# Reflow_Control_Board_Rev_2.net
KiCad netlist of a schematic drawn in EAGLE
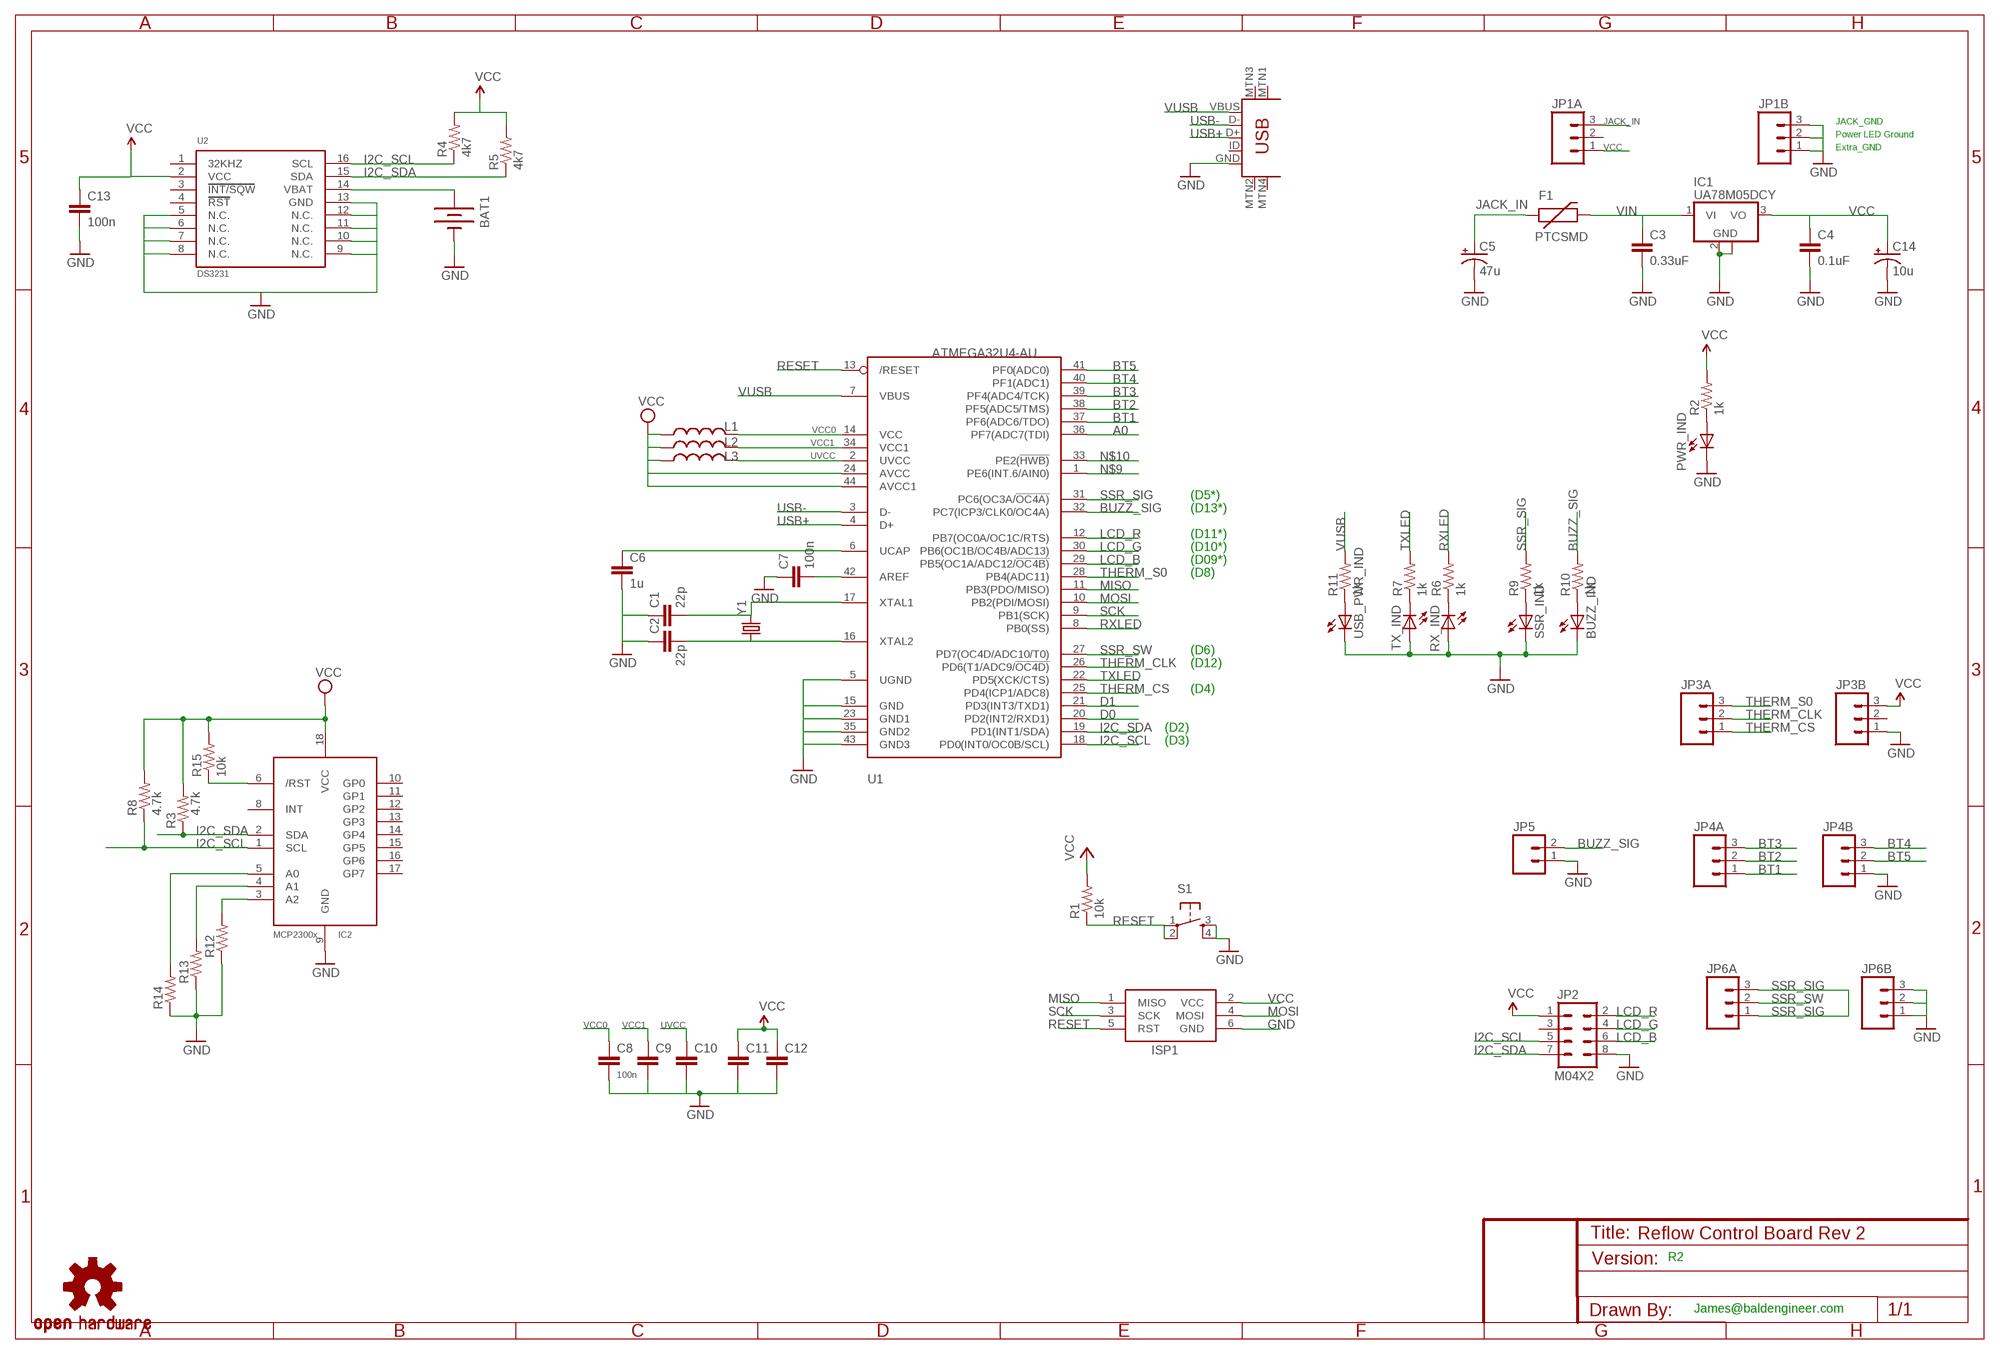
[diagram p0: schematic, sheet 1]

(export (version "E")
  (design (tool "Eeschema 10.0.6"))
  (components
    (comp (ref "BAT1")
      (value "BATTERY12MM")
      (footprint "eagle-import:BATTCON_12MM")
      (libsource (lib "eagle-import") (part "BATTERY12MM"))
    )
    (comp (ref "BUZZ_IND")
      (value "LED1206")
      (footprint "eagle-import:LED-1206")
      (libsource (lib "eagle-import") (part "LED1206"))
    )
    (comp (ref "C1")
      (value "22p")
      (footprint "eagle-import:1206")
      (libsource (lib "eagle-import") (part "CAP1206"))
    )
    (comp (ref "C2")
      (value "22p")
      (footprint "eagle-import:1206")
      (libsource (lib "eagle-import") (part "CAP1206"))
    )
    (comp (ref "C3")
      (value "0.33uF")
      (footprint "eagle-import:1206")
      (libsource (lib "eagle-import") (part "CAP1206"))
    )
    (comp (ref "C4")
      (value "0.1uF")
      (footprint "eagle-import:1206")
      (libsource (lib "eagle-import") (part "CAP1206"))
    )
    (comp (ref "C5")
      (value "47u")
      (footprint "eagle-import:D_7343-31R")
      (libsource (lib "eagle-import") (part "CPOL-USD/7343-31R"))
    )
    (comp (ref "C6")
      (value "1u")
      (footprint "eagle-import:1206")
      (libsource (lib "eagle-import") (part "CAP1206"))
    )
    (comp (ref "C7")
      (value "100n")
      (footprint "eagle-import:1206")
      (libsource (lib "eagle-import") (part "CAP1206"))
    )
    (comp (ref "C8")
      (value "100n")
      (footprint "eagle-import:1206")
      (libsource (lib "eagle-import") (part "CAP1206"))
    )
    (comp (ref "C9")
      (value "100n")
      (footprint "eagle-import:1206")
      (libsource (lib "eagle-import") (part "CAP1206"))
    )
    (comp (ref "C10")
      (value "100n")
      (footprint "eagle-import:1206")
      (libsource (lib "eagle-import") (part "CAP1206"))
    )
    (comp (ref "C11")
      (value "100n")
      (footprint "eagle-import:1206")
      (libsource (lib "eagle-import") (part "CAP1206"))
    )
    (comp (ref "C12")
      (value "100n")
      (footprint "eagle-import:1206")
      (libsource (lib "eagle-import") (part "CAP1206"))
    )
    (comp (ref "C13")
      (value "100n")
      (footprint "eagle-import:1206")
      (libsource (lib "eagle-import") (part "CAP1206"))
    )
    (comp (ref "C14")
      (value "10u")
      (footprint "eagle-import:D_7343-31R")
      (libsource (lib "eagle-import") (part "CPOL-USD/7343-31R"))
    )
    (comp (ref "F1")
      (value "PTCSMD")
      (footprint "eagle-import:PTC-1206")
      (libsource (lib "eagle-import") (part "PTCSMD"))
    )
    (comp (ref "IC1")
      (value "UA78M05DCY")
      (footprint "eagle-import:SOT223")
      (libsource (lib "eagle-import") (part "UA78MDCY05"))
    )
    (comp (ref "IC2")
      (value "MCP2300X/SO")
      (footprint "eagle-import:SO18W")
      (libsource (lib "eagle-import") (part "MCP2300X/SO"))
    )
    (comp (ref "ISP1")
      (value "AVRISP-6")
      (footprint "eagle-import:AVRISP")
      (libsource (lib "eagle-import") (part "AVRISP-6"))
    )
    (comp (ref "JP1A")
      (value "M03LOCK")
      (footprint "eagle-import:1X03_LOCK")
      (libsource (lib "eagle-import") (part "M03LOCK"))
    )
    (comp (ref "JP1B")
      (value "M03LOCK")
      (footprint "eagle-import:1X03_LOCK")
      (libsource (lib "eagle-import") (part "M03LOCK"))
    )
    (comp (ref "JP2")
      (value "M04X2")
      (footprint "eagle-import:2X4")
      (libsource (lib "eagle-import") (part "M04X2"))
    )
    (comp (ref "JP3A")
      (value "M03LOCK")
      (footprint "eagle-import:1X03_LOCK")
      (libsource (lib "eagle-import") (part "M03LOCK"))
    )
    (comp (ref "JP3B")
      (value "M03LOCK")
      (footprint "eagle-import:1X03_LOCK")
      (libsource (lib "eagle-import") (part "M03LOCK"))
    )
    (comp (ref "JP4A")
      (value "M03LOCK")
      (footprint "eagle-import:1X03_LOCK")
      (libsource (lib "eagle-import") (part "M03LOCK"))
    )
    (comp (ref "JP4B")
      (value "M03LOCK")
      (footprint "eagle-import:1X03_LOCK")
      (libsource (lib "eagle-import") (part "M03LOCK"))
    )
    (comp (ref "JP5")
      (value "M02LOCK")
      (footprint "eagle-import:1X02_LOCK")
      (libsource (lib "eagle-import") (part "M02LOCK"))
    )
    (comp (ref "JP6A")
      (value "M03LOCK")
      (footprint "eagle-import:1X03_LOCK")
      (libsource (lib "eagle-import") (part "M03LOCK"))
    )
    (comp (ref "JP6B")
      (value "M03LOCK")
      (footprint "eagle-import:1X03_LOCK")
      (libsource (lib "eagle-import") (part "M03LOCK"))
    )
    (comp (ref "L1")
      (value "INDUCTOR0805")
      (footprint "eagle-import:0805")
      (libsource (lib "eagle-import") (part "INDUCTOR0805"))
    )
    (comp (ref "L2")
      (value "INDUCTOR0805")
      (footprint "eagle-import:0805")
      (libsource (lib "eagle-import") (part "INDUCTOR0805"))
    )
    (comp (ref "L3")
      (value "INDUCTOR0805")
      (footprint "eagle-import:0805")
      (libsource (lib "eagle-import") (part "INDUCTOR0805"))
    )
    (comp (ref "PWR_IND")
      (value "LED1206")
      (footprint "eagle-import:LED-1206")
      (libsource (lib "eagle-import") (part "LED1206"))
    )
    (comp (ref "R1")
      (value "10k")
      (footprint "eagle-import:1206")
      (libsource (lib "eagle-import") (part "RESISTOR1206"))
    )
    (comp (ref "R2")
      (value "1k")
      (footprint "eagle-import:1206")
      (libsource (lib "eagle-import") (part "RESISTOR1206"))
    )
    (comp (ref "R3")
      (value "4.7k")
      (footprint "eagle-import:1206")
      (libsource (lib "eagle-import") (part "RESISTOR1206"))
    )
    (comp (ref "R4")
      (value "4k7")
      (footprint "eagle-import:1206")
      (libsource (lib "eagle-import") (part "RESISTOR1206"))
    )
    (comp (ref "R5")
      (value "4k7")
      (footprint "eagle-import:1206")
      (libsource (lib "eagle-import") (part "RESISTOR1206"))
    )
    (comp (ref "R6")
      (value "1k")
      (footprint "eagle-import:1206")
      (libsource (lib "eagle-import") (part "RESISTOR1206"))
    )
    (comp (ref "R7")
      (value "1k")
      (footprint "eagle-import:1206")
      (libsource (lib "eagle-import") (part "RESISTOR1206"))
    )
    (comp (ref "R8")
      (value "4.7k")
      (footprint "eagle-import:1206")
      (libsource (lib "eagle-import") (part "RESISTOR1206"))
    )
    (comp (ref "R9")
      (value "1k")
      (footprint "eagle-import:1206")
      (libsource (lib "eagle-import") (part "RESISTOR1206"))
    )
    (comp (ref "R10")
      (value "1k")
      (footprint "eagle-import:1206")
      (libsource (lib "eagle-import") (part "RESISTOR1206"))
    )
    (comp (ref "R11")
      (value "1k")
      (footprint "eagle-import:1206")
      (libsource (lib "eagle-import") (part "RESISTOR1206"))
    )
    (comp (ref "R12")
      (value "RESISTOR1206")
      (footprint "eagle-import:1206")
      (libsource (lib "eagle-import") (part "RESISTOR1206"))
    )
    (comp (ref "R13")
      (value "RESISTOR1206")
      (footprint "eagle-import:1206")
      (libsource (lib "eagle-import") (part "RESISTOR1206"))
    )
    (comp (ref "R14")
      (value "RESISTOR1206")
      (footprint "eagle-import:1206")
      (libsource (lib "eagle-import") (part "RESISTOR1206"))
    )
    (comp (ref "R15")
      (value "10k")
      (footprint "eagle-import:1206")
      (libsource (lib "eagle-import") (part "RESISTOR1206"))
    )
    (comp (ref "RX_IND")
      (value "LED1206")
      (footprint "eagle-import:LED-1206")
      (libsource (lib "eagle-import") (part "LED1206"))
    )
    (comp (ref "S1")
      (value "TAC_SWITCHSMD")
      (footprint "eagle-import:TACTILE_SWITCH_SMD")
      (libsource (lib "eagle-import") (part "TAC_SWITCHSMD"))
    )
    (comp (ref "SSR_IND")
      (value "LED1206")
      (footprint "eagle-import:LED-1206")
      (libsource (lib "eagle-import") (part "LED1206"))
    )
    (comp (ref "TX_IND")
      (value "LED1206")
      (footprint "eagle-import:LED-1206")
      (libsource (lib "eagle-import") (part "LED1206"))
    )
    (comp (ref "U$3")
      (value "USB-MINIB-5PIN")
      (footprint "eagle-import:USB-MINIB")
      (libsource (lib "eagle-import") (part "USB-MINIB-5PIN"))
    )
    (comp (ref "U$4")
      (value "OSHW-LOGOS")
      (footprint "eagle-import:OSHW-LOGO-S")
      (libsource (lib "eagle-import") (part "OSHW-LOGOS"))
    )
    (comp (ref "U1")
      (value "ATMEGA32U4-AU")
      (footprint "eagle-import:TQFP44")
      (libsource (lib "eagle-import") (part "ATMEGA32U4-AU"))
    )
    (comp (ref "U2")
      (value "DS3231")
      (footprint "eagle-import:SO16L")
      (libsource (lib "eagle-import") (part "DS3231"))
    )
    (comp (ref "USB_PWR_IND")
      (value "LED1206")
      (footprint "eagle-import:LED-1206")
      (libsource (lib "eagle-import") (part "LED1206"))
    )
    (comp (ref "Y1")
      (value "CRYSTALHC49US")
      (footprint "eagle-import:HC49US")
      (libsource (lib "eagle-import") (part "CRYSTALHC49US"))
    )
  )
  (nets
    (net (code "1") (name "/A0") (class "Default")
      (node (ref "U1") (pin "36") (pinfunction "PF7(ADC7(TDI)_36") (pintype "bidirectional"))
    )
    (net (code "2") (name "/BT1") (class "Default")
      (node (ref "JP4A") (pin "1") (pinfunction "1_1") (pintype "passive"))
      (node (ref "U1") (pin "37") (pinfunction "PF6(ADC6/TDO)_37") (pintype "bidirectional"))
    )
    (net (code "3") (name "/BT2") (class "Default")
      (node (ref "JP4A") (pin "2") (pinfunction "2_2") (pintype "passive"))
      (node (ref "U1") (pin "38") (pinfunction "PF5(ADC5/TMS)_38") (pintype "bidirectional"))
    )
    (net (code "4") (name "/BT3") (class "Default")
      (node (ref "JP4A") (pin "3") (pinfunction "3_3") (pintype "passive"))
      (node (ref "U1") (pin "39") (pinfunction "PF4(ADC4/TCK)_39") (pintype "bidirectional"))
    )
    (net (code "5") (name "/BT4") (class "Default")
      (node (ref "JP4B") (pin "3") (pinfunction "3_3") (pintype "passive"))
      (node (ref "U1") (pin "40") (pinfunction "PF1(ADC1)_40") (pintype "bidirectional"))
    )
    (net (code "6") (name "/BT5") (class "Default")
      (node (ref "JP4B") (pin "2") (pinfunction "2_2") (pintype "passive"))
      (node (ref "U1") (pin "41") (pinfunction "PF0(ADC0)_41") (pintype "bidirectional"))
    )
    (net (code "7") (name "/BUZZ_SIG") (class "Default")
      (node (ref "JP5") (pin "2") (pinfunction "2_2") (pintype "passive"))
      (node (ref "R10") (pin "2") (pinfunction "2_2") (pintype "passive"))
      (node (ref "U1") (pin "32") (pinfunction "PC7(ICP3/CLK0/OC4A)_32") (pintype "bidirectional"))
    )
    (net (code "8") (name "/D0") (class "Default")
      (node (ref "U1") (pin "20") (pinfunction "PD2(INT2/RXD1)_20") (pintype "bidirectional"))
    )
    (net (code "9") (name "/D1") (class "Default")
      (node (ref "U1") (pin "21") (pinfunction "PD3(INT3/TXD1)_21") (pintype "bidirectional"))
    )
    (net (code "10") (name "/I2C_SCL") (class "Default")
      (node (ref "IC2") (pin "1") (pinfunction "SCL_1") (pintype "bidirectional"))
      (node (ref "JP2") (pin "5") (pinfunction "5_5") (pintype "passive"))
      (node (ref "R4") (pin "1") (pinfunction "1_1") (pintype "passive"))
      (node (ref "R8") (pin "1") (pinfunction "1_1") (pintype "passive"))
      (node (ref "U1") (pin "18") (pinfunction "PD0(INT0/OC0B/SCL)_18") (pintype "bidirectional"))
      (node (ref "U2") (pin "16") (pinfunction "SCL_16") (pintype "bidirectional"))
    )
    (net (code "11") (name "/I2C_SDA") (class "Default")
      (node (ref "IC2") (pin "2") (pinfunction "SDA_2") (pintype "bidirectional"))
      (node (ref "JP2") (pin "7") (pinfunction "7_7") (pintype "passive"))
      (node (ref "R3") (pin "1") (pinfunction "1_1") (pintype "passive"))
      (node (ref "R5") (pin "1") (pinfunction "1_1") (pintype "passive"))
      (node (ref "U1") (pin "19") (pinfunction "PD1(INT1/SDA)_19") (pintype "bidirectional"))
      (node (ref "U2") (pin "15") (pinfunction "SDA_15") (pintype "bidirectional"))
    )
    (net (code "12") (name "/JACK_IN") (class "Default")
      (node (ref "C5") (pin "+") (pinfunction "+_+") (pintype "passive"))
      (node (ref "F1") (pin "1") (pinfunction "1_1") (pintype "bidirectional"))
      (node (ref "JP1A") (pin "3") (pinfunction "3_3") (pintype "passive"))
    )
    (net (code "13") (name "/LCD_B") (class "Default")
      (node (ref "JP2") (pin "6") (pinfunction "6_6") (pintype "passive"))
      (node (ref "U1") (pin "29") (pinfunction "PB5(OC1A/ADC12/~{OC4B})_29") (pintype "bidirectional"))
    )
    (net (code "14") (name "/LCD_G") (class "Default")
      (node (ref "JP2") (pin "4") (pinfunction "4_4") (pintype "passive"))
      (node (ref "U1") (pin "30") (pinfunction "PB6(OC1B/OC4B/ADC13)_30") (pintype "bidirectional"))
    )
    (net (code "15") (name "/LCD_R") (class "Default")
      (node (ref "JP2") (pin "2") (pinfunction "2_2") (pintype "passive"))
      (node (ref "U1") (pin "12") (pinfunction "PB7(OC0A/OC1C/RTS)_12") (pintype "bidirectional"))
    )
    (net (code "16") (name "/MISO") (class "Default")
      (node (ref "ISP1") (pin "1") (pinfunction "MISO_1") (pintype "input"))
      (node (ref "U1") (pin "11") (pinfunction "PB3(PDO/MISO)_11") (pintype "bidirectional"))
    )
    (net (code "17") (name "/MOSI") (class "Default")
      (node (ref "ISP1") (pin "4") (pinfunction "MOSI_4") (pintype "output"))
      (node (ref "U1") (pin "10") (pinfunction "PB2(PDI/MOSI)_10") (pintype "bidirectional"))
    )
    (net (code "18") (name "/N$9") (class "Default")
      (node (ref "U1") (pin "1") (pinfunction "PE6(INT.6/AIN0)_1") (pintype "bidirectional"))
    )
    (net (code "19") (name "/N$10") (class "Default")
      (node (ref "U1") (pin "33") (pinfunction "PE2(~{HWB})_33") (pintype "bidirectional"))
    )
    (net (code "20") (name "/RESET") (class "Default")
      (node (ref "ISP1") (pin "5") (pinfunction "RST_5") (pintype "output"))
      (node (ref "R1") (pin "1") (pinfunction "1_1") (pintype "passive"))
      (node (ref "S1") (pin "1") (pinfunction "1_1") (pintype "passive"))
      (node (ref "S1") (pin "2") (pinfunction "2_2") (pintype "passive"))
      (node (ref "U1") (pin "13") (pinfunction "/RESET_13") (pintype "bidirectional"))
    )
    (net (code "21") (name "/RXLED") (class "Default")
      (node (ref "R6") (pin "2") (pinfunction "2_2") (pintype "passive"))
      (node (ref "U1") (pin "8") (pinfunction "PB0(SS)_8") (pintype "bidirectional"))
    )
    (net (code "22") (name "/SCK") (class "Default")
      (node (ref "ISP1") (pin "3") (pinfunction "SCK_3") (pintype "output"))
      (node (ref "U1") (pin "9") (pinfunction "PB1(SCK)_9") (pintype "bidirectional"))
    )
    (net (code "23") (name "/SSR_SIG") (class "Default")
      (node (ref "JP6A") (pin "1") (pinfunction "1_1") (pintype "passive"))
      (node (ref "JP6A") (pin "3") (pinfunction "3_3") (pintype "passive"))
      (node (ref "R9") (pin "2") (pinfunction "2_2") (pintype "passive"))
      (node (ref "U1") (pin "31") (pinfunction "PC6(OC3A/~{OC4A})_31") (pintype "bidirectional"))
    )
    (net (code "24") (name "/SSR_SW") (class "Default")
      (node (ref "JP6A") (pin "2") (pinfunction "2_2") (pintype "passive"))
      (node (ref "U1") (pin "27") (pinfunction "PD7(OC4D/ADC10/T0)_27") (pintype "bidirectional"))
    )
    (net (code "25") (name "/THERM_CLK") (class "Default")
      (node (ref "JP3A") (pin "2") (pinfunction "2_2") (pintype "passive"))
      (node (ref "U1") (pin "26") (pinfunction "PD6(T1/ADC9/~{OC4D})_26") (pintype "bidirectional"))
    )
    (net (code "26") (name "/THERM_CS") (class "Default")
      (node (ref "JP3A") (pin "1") (pinfunction "1_1") (pintype "passive"))
      (node (ref "U1") (pin "25") (pinfunction "PD4(ICP1/ADC8)_25") (pintype "bidirectional"))
    )
    (net (code "27") (name "/THERM_S0") (class "Default")
      (node (ref "JP3A") (pin "3") (pinfunction "3_3") (pintype "passive"))
      (node (ref "U1") (pin "28") (pinfunction "PB4(ADC11)_28") (pintype "bidirectional"))
    )
    (net (code "28") (name "/TXLED") (class "Default")
      (node (ref "R7") (pin "2") (pinfunction "2_2") (pintype "passive"))
      (node (ref "U1") (pin "22") (pinfunction "PD5(XCK/CTS)_22") (pintype "bidirectional"))
    )
    (net (code "29") (name "/USB+") (class "Default")
      (node (ref "U$3") (pin "D+") (pinfunction "D+_D+") (pintype "bidirectional"))
      (node (ref "U1") (pin "4") (pinfunction "D+_4") (pintype "bidirectional"))
    )
    (net (code "30") (name "/USB-") (class "Default")
      (node (ref "U$3") (pin "D-") (pinfunction "D-_D-") (pintype "bidirectional"))
      (node (ref "U1") (pin "3") (pinfunction "D-_3") (pintype "bidirectional"))
    )
    (net (code "31") (name "/UVCC") (class "Default")
      (node (ref "C10") (pin "1") (pinfunction "1_1") (pintype "passive"))
      (node (ref "L3") (pin "2") (pinfunction "2_2") (pintype "passive"))
      (node (ref "U1") (pin "2") (pinfunction "UVCC_2") (pintype "bidirectional"))
    )
    (net (code "32") (name "/VCC0") (class "Default")
      (node (ref "C8") (pin "1") (pinfunction "1_1") (pintype "passive"))
      (node (ref "L1") (pin "2") (pinfunction "2_2") (pintype "passive"))
      (node (ref "U1") (pin "14") (pinfunction "VCC_14") (pintype "bidirectional"))
    )
    (net (code "33") (name "/VCC1") (class "Default")
      (node (ref "C9") (pin "1") (pinfunction "1_1") (pintype "passive"))
      (node (ref "L2") (pin "2") (pinfunction "2_2") (pintype "passive"))
      (node (ref "U1") (pin "34") (pinfunction "VCC1_34") (pintype "bidirectional"))
    )
    (net (code "34") (name "/VIN") (class "Default")
      (node (ref "C3") (pin "1") (pinfunction "1_1") (pintype "passive"))
      (node (ref "F1") (pin "2") (pinfunction "2_2") (pintype "bidirectional"))
      (node (ref "IC1") (pin "1") (pinfunction "VI_1") (pintype "input"))
    )
    (net (code "35") (name "/VUSB") (class "Default")
      (node (ref "R11") (pin "2") (pinfunction "2_2") (pintype "passive"))
      (node (ref "U$3") (pin "VBUS") (pinfunction "VBUS_VBUS") (pintype "bidirectional"))
      (node (ref "U1") (pin "7") (pinfunction "VBUS_7") (pintype "bidirectional"))
    )
    (net (code "36") (name "GND") (class "Default")
      (node (ref "BAT1") (pin "GND") (pinfunction "-_GND") (pintype "power_in"))
      (node (ref "BUZZ_IND") (pin "C") (pinfunction "C_C") (pintype "passive"))
      (node (ref "C1") (pin "1") (pinfunction "1_1") (pintype "passive"))
      (node (ref "C10") (pin "2") (pinfunction "2_2") (pintype "passive"))
      (node (ref "C11") (pin "2") (pinfunction "2_2") (pintype "passive"))
      (node (ref "C12") (pin "2") (pinfunction "2_2") (pintype "passive"))
      (node (ref "C13") (pin "2") (pinfunction "2_2") (pintype "passive"))
      (node (ref "C14") (pin "-") (pinfunction "-_-") (pintype "passive"))
      (node (ref "C2") (pin "1") (pinfunction "1_1") (pintype "passive"))
      (node (ref "C3") (pin "2") (pinfunction "2_2") (pintype "passive"))
      (node (ref "C4") (pin "2") (pinfunction "2_2") (pintype "passive"))
      (node (ref "C5") (pin "-") (pinfunction "-_-") (pintype "passive"))
      (node (ref "C6") (pin "2") (pinfunction "2_2") (pintype "passive"))
      (node (ref "C7") (pin "1") (pinfunction "1_1") (pintype "passive"))
      (node (ref "C8") (pin "2") (pinfunction "2_2") (pintype "passive"))
      (node (ref "C9") (pin "2") (pinfunction "2_2") (pintype "passive"))
      (node (ref "IC1") (pin "2") (pinfunction "GND_2") (pintype "passive"))
      (node (ref "IC1") (pin "4") (pinfunction "GND_4") (pintype "passive"))
      (node (ref "IC2") (pin "9") (pinfunction "GND_9") (pintype "power_in"))
      (node (ref "ISP1") (pin "6") (pinfunction "GND_6") (pintype "power_in"))
      (node (ref "JP1B") (pin "1") (pinfunction "1_1") (pintype "passive"))
      (node (ref "JP1B") (pin "2") (pinfunction "2_2") (pintype "passive"))
      (node (ref "JP1B") (pin "3") (pinfunction "3_3") (pintype "passive"))
      (node (ref "JP2") (pin "8") (pinfunction "8_8") (pintype "passive"))
      (node (ref "JP3B") (pin "1") (pinfunction "1_1") (pintype "passive"))
      (node (ref "JP4B") (pin "1") (pinfunction "1_1") (pintype "passive"))
      (node (ref "JP5") (pin "1") (pinfunction "1_1") (pintype "passive"))
      (node (ref "JP6B") (pin "1") (pinfunction "1_1") (pintype "passive"))
      (node (ref "JP6B") (pin "2") (pinfunction "2_2") (pintype "passive"))
      (node (ref "JP6B") (pin "3") (pinfunction "3_3") (pintype "passive"))
      (node (ref "PWR_IND") (pin "C") (pinfunction "C_C") (pintype "passive"))
      (node (ref "R12") (pin "1") (pinfunction "1_1") (pintype "passive"))
      (node (ref "R13") (pin "1") (pinfunction "1_1") (pintype "passive"))
      (node (ref "R14") (pin "1") (pinfunction "1_1") (pintype "passive"))
      (node (ref "RX_IND") (pin "A") (pinfunction "A_A") (pintype "passive"))
      (node (ref "S1") (pin "3") (pinfunction "3_3") (pintype "passive"))
      (node (ref "S1") (pin "4") (pinfunction "4_4") (pintype "passive"))
      (node (ref "SSR_IND") (pin "C") (pinfunction "C_C") (pintype "passive"))
      (node (ref "TX_IND") (pin "A") (pinfunction "A_A") (pintype "passive"))
      (node (ref "U$3") (pin "GND") (pinfunction "GND_GND") (pintype "bidirectional"))
      (node (ref "U1") (pin "15") (pinfunction "GND_15") (pintype "bidirectional"))
      (node (ref "U1") (pin "23") (pinfunction "GND1_23") (pintype "bidirectional"))
      (node (ref "U1") (pin "35") (pinfunction "GND2_35") (pintype "bidirectional"))
      (node (ref "U1") (pin "43") (pinfunction "GND3_43") (pintype "bidirectional"))
      (node (ref "U1") (pin "5") (pinfunction "UGND_5") (pintype "bidirectional"))
      (node (ref "U2") (pin "10") (pinfunction "N.C._10") (pintype "bidirectional"))
      (node (ref "U2") (pin "11") (pinfunction "N.C._11") (pintype "bidirectional"))
      (node (ref "U2") (pin "12") (pinfunction "N.C._12") (pintype "bidirectional"))
      (node (ref "U2") (pin "13") (pinfunction "GND_13") (pintype "power_in"))
      (node (ref "U2") (pin "5") (pinfunction "N.C._5") (pintype "bidirectional"))
      (node (ref "U2") (pin "6") (pinfunction "N.C._6") (pintype "bidirectional"))
      (node (ref "U2") (pin "7") (pinfunction "N.C._7") (pintype "bidirectional"))
      (node (ref "U2") (pin "8") (pinfunction "N.C._8") (pintype "bidirectional"))
      (node (ref "U2") (pin "9") (pinfunction "N.C._9") (pintype "bidirectional"))
      (node (ref "USB_PWR_IND") (pin "C") (pinfunction "C_C") (pintype "passive"))
    )
    (net (code "37") (name "Net-(BAT1-+)") (class "Default")
      (node (ref "BAT1") (pin "PWR@2") (pinfunction "+_PWR@2") (pintype "power_in"))
      (node (ref "U2") (pin "14") (pinfunction "VBAT_14") (pintype "power_in"))
    )
    (net (code "38") (name "Net-(BUZZ_IND-PadA)") (class "Default")
      (node (ref "BUZZ_IND") (pin "A") (pinfunction "A_A") (pintype "passive"))
      (node (ref "R10") (pin "1") (pinfunction "1_1") (pintype "passive"))
    )
    (net (code "39") (name "Net-(IC2-A0)") (class "Default")
      (node (ref "IC2") (pin "5") (pinfunction "A0_5") (pintype "input"))
      (node (ref "R14") (pin "2") (pinfunction "2_2") (pintype "passive"))
    )
    (net (code "40") (name "Net-(IC2-A1)") (class "Default")
      (node (ref "IC2") (pin "4") (pinfunction "A1_4") (pintype "input"))
      (node (ref "R13") (pin "2") (pinfunction "2_2") (pintype "passive"))
    )
    (net (code "41") (name "Net-(IC2-A2)") (class "Default")
      (node (ref "IC2") (pin "3") (pinfunction "A2_3") (pintype "input"))
      (node (ref "R12") (pin "2") (pinfunction "2_2") (pintype "passive"))
    )
    (net (code "42") (name "Net-(IC2-{slash}RST)") (class "Default")
      (node (ref "IC2") (pin "6") (pinfunction "/RST_6") (pintype "input"))
      (node (ref "R15") (pin "1") (pinfunction "1_1") (pintype "passive"))
    )
    (net (code "43") (name "Net-(PWR_IND-PadA)") (class "Default")
      (node (ref "PWR_IND") (pin "A") (pinfunction "A_A") (pintype "passive"))
      (node (ref "R2") (pin "1") (pinfunction "1_1") (pintype "passive"))
    )
    (net (code "44") (name "Net-(R6-Pad1)") (class "Default")
      (node (ref "R6") (pin "1") (pinfunction "1_1") (pintype "passive"))
      (node (ref "RX_IND") (pin "C") (pinfunction "C_C") (pintype "passive"))
    )
    (net (code "45") (name "Net-(R7-Pad1)") (class "Default")
      (node (ref "R7") (pin "1") (pinfunction "1_1") (pintype "passive"))
      (node (ref "TX_IND") (pin "C") (pinfunction "C_C") (pintype "passive"))
    )
    (net (code "46") (name "Net-(R9-Pad1)") (class "Default")
      (node (ref "R9") (pin "1") (pinfunction "1_1") (pintype "passive"))
      (node (ref "SSR_IND") (pin "A") (pinfunction "A_A") (pintype "passive"))
    )
    (net (code "47") (name "Net-(R11-Pad1)") (class "Default")
      (node (ref "R11") (pin "1") (pinfunction "1_1") (pintype "passive"))
      (node (ref "USB_PWR_IND") (pin "A") (pinfunction "A_A") (pintype "passive"))
    )
    (net (code "48") (name "Net-(U1-AREF)") (class "Default")
      (node (ref "C7") (pin "2") (pinfunction "2_2") (pintype "passive"))
      (node (ref "U1") (pin "42") (pinfunction "AREF_42") (pintype "bidirectional"))
    )
    (net (code "49") (name "Net-(U1-UCAP)") (class "Default")
      (node (ref "C6") (pin "1") (pinfunction "1_1") (pintype "passive"))
      (node (ref "U1") (pin "6") (pinfunction "UCAP_6") (pintype "bidirectional"))
    )
    (net (code "50") (name "Net-(U1-XTAL1)") (class "Default")
      (node (ref "C1") (pin "2") (pinfunction "2_2") (pintype "passive"))
      (node (ref "U1") (pin "17") (pinfunction "XTAL1_17") (pintype "bidirectional"))
      (node (ref "Y1") (pin "2") (pinfunction "2_2") (pintype "passive"))
    )
    (net (code "51") (name "Net-(U1-XTAL2)") (class "Default")
      (node (ref "C2") (pin "2") (pinfunction "2_2") (pintype "passive"))
      (node (ref "U1") (pin "16") (pinfunction "XTAL2_16") (pintype "bidirectional"))
      (node (ref "Y1") (pin "1") (pinfunction "1_1") (pintype "passive"))
    )
    (net (code "52") (name "VCC") (class "Default")
      (node (ref "C11") (pin "1") (pinfunction "1_1") (pintype "passive"))
      (node (ref "C12") (pin "1") (pinfunction "1_1") (pintype "passive"))
      (node (ref "C13") (pin "1") (pinfunction "1_1") (pintype "passive"))
      (node (ref "C14") (pin "+") (pinfunction "+_+") (pintype "passive"))
      (node (ref "C4") (pin "1") (pinfunction "1_1") (pintype "passive"))
      (node (ref "IC1") (pin "3") (pinfunction "VO_3") (pintype "passive"))
      (node (ref "IC2") (pin "18") (pinfunction "VCC_18") (pintype "power_in"))
      (node (ref "ISP1") (pin "2") (pinfunction "VCC_2") (pintype "power_in"))
      (node (ref "JP1A") (pin "1") (pinfunction "1_1") (pintype "passive"))
      (node (ref "JP2") (pin "1") (pinfunction "1_1") (pintype "passive"))
      (node (ref "JP3B") (pin "3") (pinfunction "3_3") (pintype "passive"))
      (node (ref "L1") (pin "1") (pinfunction "1_1") (pintype "passive"))
      (node (ref "L2") (pin "1") (pinfunction "1_1") (pintype "passive"))
      (node (ref "L3") (pin "1") (pinfunction "1_1") (pintype "passive"))
      (node (ref "R1") (pin "2") (pinfunction "2_2") (pintype "passive"))
      (node (ref "R15") (pin "2") (pinfunction "2_2") (pintype "passive"))
      (node (ref "R2") (pin "2") (pinfunction "2_2") (pintype "passive"))
      (node (ref "R3") (pin "2") (pinfunction "2_2") (pintype "passive"))
      (node (ref "R4") (pin "2") (pinfunction "2_2") (pintype "passive"))
      (node (ref "R5") (pin "2") (pinfunction "2_2") (pintype "passive"))
      (node (ref "R8") (pin "2") (pinfunction "2_2") (pintype "passive"))
      (node (ref "U1") (pin "24") (pinfunction "AVCC_24") (pintype "bidirectional"))
      (node (ref "U1") (pin "44") (pinfunction "AVCC1_44") (pintype "bidirectional"))
      (node (ref "U2") (pin "2") (pinfunction "VCC_2") (pintype "power_in"))
    )
    (net (code "53") (name "unconnected-(IC2-GP0-Pad10)") (class "Default")
      (node (ref "IC2") (pin "10") (pinfunction "GP0_10") (pintype "bidirectional"))
    )
    (net (code "54") (name "unconnected-(IC2-GP1-Pad11)") (class "Default")
      (node (ref "IC2") (pin "11") (pinfunction "GP1_11") (pintype "bidirectional"))
    )
    (net (code "55") (name "unconnected-(IC2-GP2-Pad12)") (class "Default")
      (node (ref "IC2") (pin "12") (pinfunction "GP2_12") (pintype "bidirectional"))
    )
    (net (code "56") (name "unconnected-(IC2-GP3-Pad13)") (class "Default")
      (node (ref "IC2") (pin "13") (pinfunction "GP3_13") (pintype "bidirectional"))
    )
    (net (code "57") (name "unconnected-(IC2-GP4-Pad14)") (class "Default")
      (node (ref "IC2") (pin "14") (pinfunction "GP4_14") (pintype "bidirectional"))
    )
    (net (code "58") (name "unconnected-(IC2-GP5-Pad15)") (class "Default")
      (node (ref "IC2") (pin "15") (pinfunction "GP5_15") (pintype "bidirectional"))
    )
    (net (code "59") (name "unconnected-(IC2-GP6-Pad16)") (class "Default")
      (node (ref "IC2") (pin "16") (pinfunction "GP6_16") (pintype "bidirectional"))
    )
    (net (code "60") (name "unconnected-(IC2-GP7-Pad17)") (class "Default")
      (node (ref "IC2") (pin "17") (pinfunction "GP7_17") (pintype "bidirectional"))
    )
    (net (code "61") (name "unconnected-(IC2-INT-Pad8)") (class "Default")
      (node (ref "IC2") (pin "8") (pinfunction "INT_8") (pintype "output"))
    )
    (net (code "62") (name "unconnected-(JP1A-Pad2)") (class "Default")
      (node (ref "JP1A") (pin "2") (pinfunction "2_2") (pintype "passive"))
    )
    (net (code "63") (name "unconnected-(JP2-Pad3)") (class "Default")
      (node (ref "JP2") (pin "3") (pinfunction "3_3") (pintype "passive"))
    )
    (net (code "64") (name "unconnected-(JP3B-Pad2)") (class "Default")
      (node (ref "JP3B") (pin "2") (pinfunction "2_2") (pintype "passive"))
    )
    (net (code "65") (name "unconnected-(U$3-MTN1-PadMTN3)") (class "Default")
      (node (ref "U$3") (pin "MTN3") (pinfunction "MTN1_MTN3") (pintype "bidirectional"))
    )
    (net (code "66") (name "unconnected-(U$3-MTN2-PadMTN1)") (class "Default")
      (node (ref "U$3") (pin "MTN1") (pinfunction "MTN2_MTN1") (pintype "bidirectional"))
    )
    (net (code "67") (name "unconnected-(U$3-MTN3-PadMTN2)") (class "Default")
      (node (ref "U$3") (pin "MTN2") (pinfunction "MTN3_MTN2") (pintype "bidirectional"))
    )
    (net (code "68") (name "unconnected-(U$3-PadID)") (class "Default")
      (node (ref "U$3") (pin "ID") (pinfunction "ID_ID") (pintype "bidirectional"))
    )
    (net (code "69") (name "unconnected-(U$3-PadMTN4)") (class "Default")
      (node (ref "U$3") (pin "MTN4") (pinfunction "MTN4_MTN4") (pintype "bidirectional"))
    )
    (net (code "70") (name "unconnected-(U2-32KHZ-Pad1)") (class "Default")
      (node (ref "U2") (pin "1") (pinfunction "32KHZ_1") (pintype "bidirectional"))
    )
    (net (code "71") (name "unconnected-(U2-INT{slash}SQW-Pad3)") (class "Default")
      (node (ref "U2") (pin "3") (pinfunction "INT/SQW_3") (pintype "bidirectional"))
    )
    (net (code "72") (name "unconnected-(U2-RST-Pad4)") (class "Default")
      (node (ref "U2") (pin "4") (pinfunction "RST_4") (pintype "bidirectional"))
    )
  )
)
